# Sheet2.net
KiCad netlist of a schematic drawn in Altium Designer
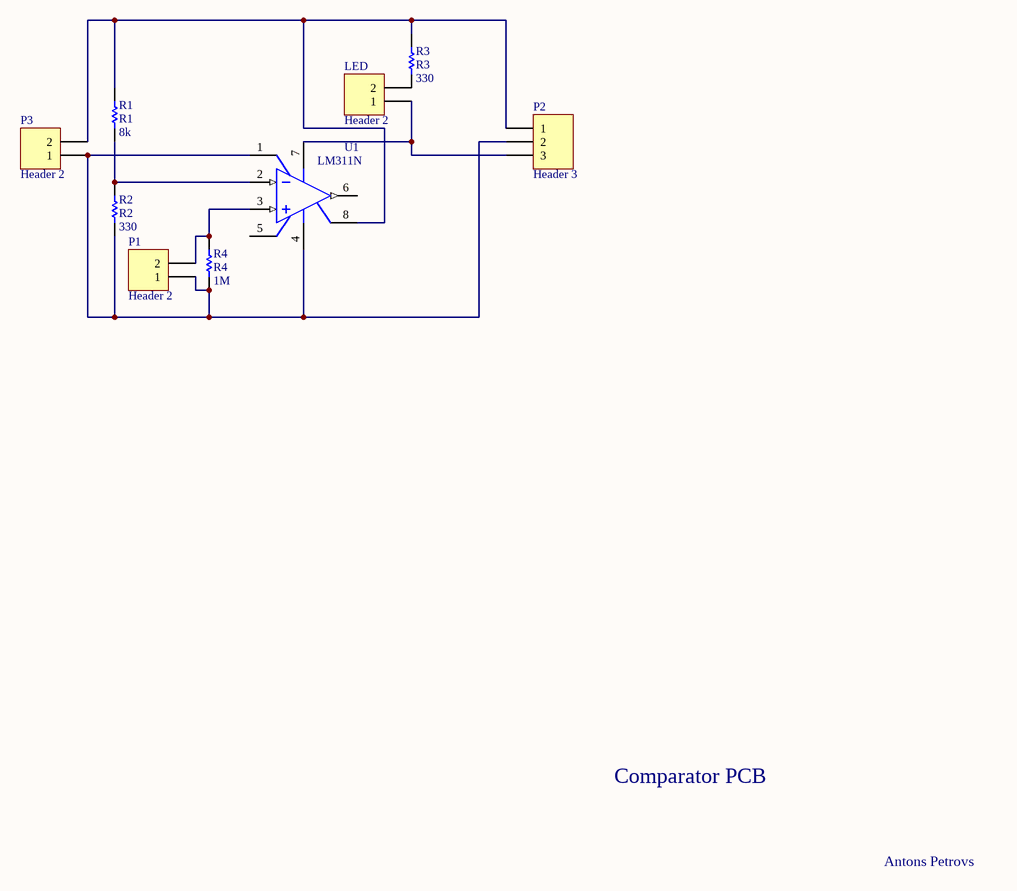
[diagram p0: Sheet2.SchDoc]

(export (version "E")
  (design (tool "Eeschema 10.0.6"))
  (components
    (comp (ref "LED")
      (value "Header 2")
      (footprint "HDR1X2")
      (description "Header, 2-Pin")
      (fields (field (name "PUBLISHER") "Altium Limited"))
      (libsource (lib "Miscellaneous Connectors") (part "Header 2"))
    )
    (comp (ref "P1")
      (value "Header 2")
      (footprint "HDR1X2")
      (description "Header, 2-Pin")
      (fields (field (name "PUBLISHER") "Altium Limited"))
      (libsource (lib "Miscellaneous Connectors") (part "Header 2"))
    )
    (comp (ref "P2")
      (value "Header 3")
      (footprint "HDR1X3")
      (description "Header, 3-Pin")
      (fields (field (name "PUBLISHER") "Altium Limited"))
      (libsource (lib "Miscellaneous Connectors") (part "Header 3"))
    )
    (comp (ref "P3")
      (value "Header 2")
      (footprint "HDR1X2")
      (description "Header, 2-Pin")
      (fields (field (name "PUBLISHER") "Altium Limited"))
      (libsource (lib "Miscellaneous Connectors") (part "Header 2"))
    )
    (comp (ref "R1")
      (value "R1")
      (footprint "AXIAL-0.3")
      (description "Resistor")
      (fields (field (name "ALTIUM_VALUE") "8k") (field (name "PUBLISHER") "Altium Limited"))
      (libsource (lib "Miscellaneous Devices") (part "Res1"))
    )
    (comp (ref "R2")
      (value "R2")
      (footprint "AXIAL-0.3")
      (description "Resistor")
      (fields (field (name "ALTIUM_VALUE") "330") (field (name "PUBLISHER") "Altium Limited"))
      (libsource (lib "Miscellaneous Devices") (part "Res1"))
    )
    (comp (ref "R3")
      (value "R3")
      (footprint "AXIAL-0.3")
      (description "Resistor")
      (fields (field (name "ALTIUM_VALUE") "330") (field (name "PUBLISHER") "Altium Limited"))
      (libsource (lib "Miscellaneous Devices") (part "Res1"))
    )
    (comp (ref "R4")
      (value "R4")
      (footprint "AXIAL-0.3")
      (description "Resistor")
      (fields (field (name "ALTIUM_VALUE") "1M") (field (name "PUBLISHER") "Altium Limited"))
      (libsource (lib "Miscellaneous Devices") (part "Res1"))
    )
    (comp (ref "U1")
      (value "LM311N")
      (footprint "N08E")
      (description "Operational Amplifier, 8-pin MDIP")
      (fields
        (field (name "PARTNUMBER") "LM741CN")
        (field (name "MANUFACTURER") "National Semiconductor")
        (field (name "PUBLISHER") "Altium Limited")
      )
      (libsource (lib "NSC Amplifier") (part "LM741CN"))
    )
  )
  (nets
    (net (code "1") (name "Net-(LED-Pad2)") (class "Default")
      (node (ref "LED") (pin "2") (pinfunction "2_2") (pintype "passive"))
      (node (ref "R3") (pin "1") (pinfunction "1_1") (pintype "passive"))
    )
    (net (code "2") (name "Net-(U1-IN+)") (class "Default")
      (node (ref "P1") (pin "2") (pinfunction "2_2") (pintype "passive"))
      (node (ref "R4") (pin "2") (pinfunction "2_2") (pintype "passive"))
      (node (ref "U1") (pin "3") (pinfunction "IN+_3") (pintype "input"))
    )
    (net (code "3") (name "Net-(U1-IN-)") (class "Default")
      (node (ref "R1") (pin "1") (pinfunction "1_1") (pintype "passive"))
      (node (ref "R2") (pin "2") (pinfunction "2_2") (pintype "passive"))
      (node (ref "U1") (pin "2") (pinfunction "IN-_2") (pintype "input"))
    )
    (net (code "4") (name "Net-(U1-NC)") (class "Default")
      (node (ref "P2") (pin "1") (pinfunction "1_1") (pintype "passive"))
      (node (ref "P3") (pin "2") (pinfunction "2_2") (pintype "passive"))
      (node (ref "R1") (pin "2") (pinfunction "2_2") (pintype "passive"))
      (node (ref "R3") (pin "2") (pinfunction "2_2") (pintype "passive"))
      (node (ref "U1") (pin "8") (pinfunction "NC_8") (pintype "passive"))
    )
    (net (code "5") (name "Net-(U1-V+)") (class "Default")
      (node (ref "LED") (pin "1") (pinfunction "1_1") (pintype "passive"))
      (node (ref "P2") (pin "3") (pinfunction "3_3") (pintype "passive"))
      (node (ref "U1") (pin "7") (pinfunction "V+_7") (pintype "power_in"))
    )
    (net (code "6") (name "Net-(U1-V-)") (class "Default")
      (node (ref "P1") (pin "1") (pinfunction "1_1") (pintype "passive"))
      (node (ref "P2") (pin "2") (pinfunction "2_2") (pintype "passive"))
      (node (ref "P3") (pin "1") (pinfunction "1_1") (pintype "passive"))
      (node (ref "R2") (pin "1") (pinfunction "1_1") (pintype "passive"))
      (node (ref "R4") (pin "1") (pinfunction "1_1") (pintype "passive"))
      (node (ref "U1") (pin "1") (pinfunction "OFS_NULL_1") (pintype "passive"))
      (node (ref "U1") (pin "4") (pinfunction "V-_4") (pintype "power_in"))
    )
    (net (code "7") (name "unconnected-(U1-OFS_NULL-Pad5)") (class "Default")
      (node (ref "U1") (pin "5") (pinfunction "OFS_NULL_5") (pintype "passive"))
    )
    (net (code "8") (name "unconnected-(U1-OUT-Pad6)") (class "Default")
      (node (ref "U1") (pin "6") (pinfunction "OUT_6") (pintype "output"))
    )
  )
)
